# adapter.net
KiCad netlist of a schematic drawn in EAGLE
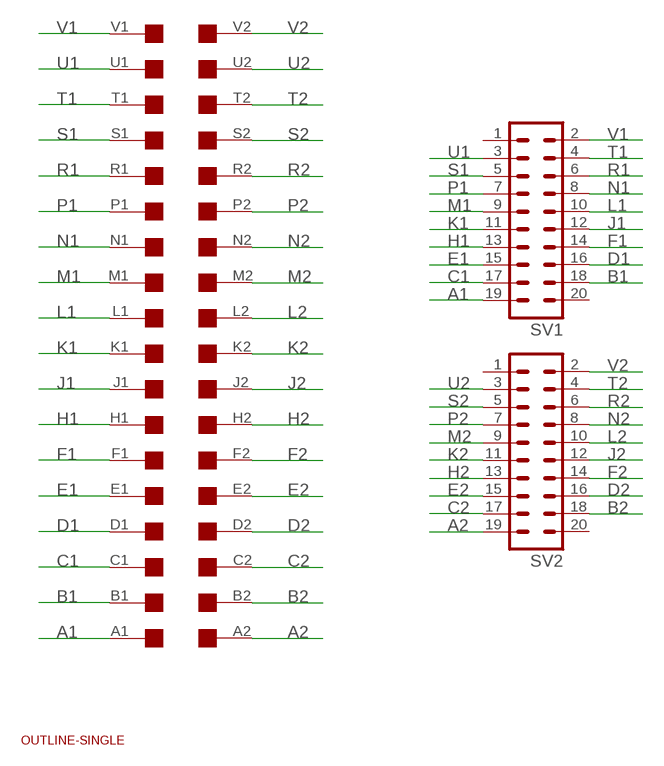
[diagram p0: schematic, sheet 1]

(export (version "E")
  (design (tool "Eeschema 10.0.6"))
  (components
    (comp (ref "SV1")
      (value "MA10-2W")
      (footprint "eagle-import:MA10-2W")
      (libsource (lib "eagle-import") (part "MA10-2W"))
    )
    (comp (ref "SV2")
      (value "MA10-2W")
      (footprint "eagle-import:MA10-2W")
      (libsource (lib "eagle-import") (part "MA10-2W"))
    )
    (comp (ref "U$1")
      (value "OUTLINE-SINGLE")
      (footprint "eagle-import:SINGLE")
      (libsource (lib "eagle-import") (part "OUTLINE-SINGLE"))
    )
    (comp (ref "U$2")
      (value "SINGLE")
      (footprint "eagle-import:EDGE-CON2")
      (libsource (lib "eagle-import") (part "SINGLE"))
    )
  )
  (nets
    (net (code "1") (name "/A1") (class "Default")
      (node (ref "SV1") (pin "19") (pinfunction "19_19") (pintype "passive"))
      (node (ref "U$2") (pin "A1") (pinfunction "1_A1") (pintype "bidirectional"))
    )
    (net (code "2") (name "/A2") (class "Default")
      (node (ref "SV2") (pin "19") (pinfunction "19_19") (pintype "passive"))
      (node (ref "U$2") (pin "A2") (pinfunction "1_A2") (pintype "bidirectional"))
    )
    (net (code "3") (name "/B1") (class "Default")
      (node (ref "SV1") (pin "18") (pinfunction "18_18") (pintype "passive"))
      (node (ref "U$2") (pin "B1") (pinfunction "1_B1") (pintype "bidirectional"))
    )
    (net (code "4") (name "/B2") (class "Default")
      (node (ref "SV2") (pin "18") (pinfunction "18_18") (pintype "passive"))
      (node (ref "U$2") (pin "B2") (pinfunction "1_B2") (pintype "bidirectional"))
    )
    (net (code "5") (name "/C1") (class "Default")
      (node (ref "SV1") (pin "17") (pinfunction "17_17") (pintype "passive"))
      (node (ref "U$2") (pin "C1") (pinfunction "1_C1") (pintype "bidirectional"))
    )
    (net (code "6") (name "/C2") (class "Default")
      (node (ref "SV2") (pin "17") (pinfunction "17_17") (pintype "passive"))
      (node (ref "U$2") (pin "C2") (pinfunction "1_C2") (pintype "bidirectional"))
    )
    (net (code "7") (name "/D1") (class "Default")
      (node (ref "SV1") (pin "16") (pinfunction "16_16") (pintype "passive"))
      (node (ref "U$2") (pin "D1") (pinfunction "1_D1") (pintype "bidirectional"))
    )
    (net (code "8") (name "/D2") (class "Default")
      (node (ref "SV2") (pin "16") (pinfunction "16_16") (pintype "passive"))
      (node (ref "U$2") (pin "D2") (pinfunction "1_D2") (pintype "bidirectional"))
    )
    (net (code "9") (name "/E1") (class "Default")
      (node (ref "SV1") (pin "15") (pinfunction "15_15") (pintype "passive"))
      (node (ref "U$2") (pin "E1") (pinfunction "1_E1") (pintype "bidirectional"))
    )
    (net (code "10") (name "/E2") (class "Default")
      (node (ref "SV2") (pin "15") (pinfunction "15_15") (pintype "passive"))
      (node (ref "U$2") (pin "E2") (pinfunction "1_E2") (pintype "bidirectional"))
    )
    (net (code "11") (name "/F1") (class "Default")
      (node (ref "SV1") (pin "14") (pinfunction "14_14") (pintype "passive"))
      (node (ref "U$2") (pin "F1") (pinfunction "1_F1") (pintype "bidirectional"))
    )
    (net (code "12") (name "/F2") (class "Default")
      (node (ref "SV2") (pin "14") (pinfunction "14_14") (pintype "passive"))
      (node (ref "U$2") (pin "F2") (pinfunction "1_F2") (pintype "bidirectional"))
    )
    (net (code "13") (name "/H1") (class "Default")
      (node (ref "SV1") (pin "13") (pinfunction "13_13") (pintype "passive"))
      (node (ref "U$2") (pin "H1") (pinfunction "1_H1") (pintype "bidirectional"))
    )
    (net (code "14") (name "/H2") (class "Default")
      (node (ref "SV2") (pin "13") (pinfunction "13_13") (pintype "passive"))
      (node (ref "U$2") (pin "H2") (pinfunction "1_H2") (pintype "bidirectional"))
    )
    (net (code "15") (name "/J1") (class "Default")
      (node (ref "SV1") (pin "12") (pinfunction "12_12") (pintype "passive"))
      (node (ref "U$2") (pin "J1") (pinfunction "1_J1") (pintype "bidirectional"))
    )
    (net (code "16") (name "/J2") (class "Default")
      (node (ref "SV2") (pin "12") (pinfunction "12_12") (pintype "passive"))
      (node (ref "U$2") (pin "J2") (pinfunction "1_J2") (pintype "bidirectional"))
    )
    (net (code "17") (name "/K1") (class "Default")
      (node (ref "SV1") (pin "11") (pinfunction "11_11") (pintype "passive"))
      (node (ref "U$2") (pin "K1") (pinfunction "1_K1") (pintype "bidirectional"))
    )
    (net (code "18") (name "/K2") (class "Default")
      (node (ref "SV2") (pin "11") (pinfunction "11_11") (pintype "passive"))
      (node (ref "U$2") (pin "K2") (pinfunction "1_K2") (pintype "bidirectional"))
    )
    (net (code "19") (name "/L1") (class "Default")
      (node (ref "SV1") (pin "10") (pinfunction "10_10") (pintype "passive"))
      (node (ref "U$2") (pin "L1") (pinfunction "1_L1") (pintype "bidirectional"))
    )
    (net (code "20") (name "/L2") (class "Default")
      (node (ref "SV2") (pin "10") (pinfunction "10_10") (pintype "passive"))
      (node (ref "U$2") (pin "L2") (pinfunction "1_L2") (pintype "bidirectional"))
    )
    (net (code "21") (name "/M1") (class "Default")
      (node (ref "SV1") (pin "9") (pinfunction "9_9") (pintype "passive"))
      (node (ref "U$2") (pin "M1") (pinfunction "1_M1") (pintype "bidirectional"))
    )
    (net (code "22") (name "/M2") (class "Default")
      (node (ref "SV2") (pin "9") (pinfunction "9_9") (pintype "passive"))
      (node (ref "U$2") (pin "M2") (pinfunction "1_M2") (pintype "bidirectional"))
    )
    (net (code "23") (name "/N1") (class "Default")
      (node (ref "SV1") (pin "8") (pinfunction "8_8") (pintype "passive"))
      (node (ref "U$2") (pin "N1") (pinfunction "1_N1") (pintype "bidirectional"))
    )
    (net (code "24") (name "/N2") (class "Default")
      (node (ref "SV2") (pin "8") (pinfunction "8_8") (pintype "passive"))
      (node (ref "U$2") (pin "N2") (pinfunction "1_N2") (pintype "bidirectional"))
    )
    (net (code "25") (name "/P1") (class "Default")
      (node (ref "SV1") (pin "7") (pinfunction "7_7") (pintype "passive"))
      (node (ref "U$2") (pin "P1") (pinfunction "1_P1") (pintype "bidirectional"))
    )
    (net (code "26") (name "/P2") (class "Default")
      (node (ref "SV2") (pin "7") (pinfunction "7_7") (pintype "passive"))
      (node (ref "U$2") (pin "P2") (pinfunction "1_P2") (pintype "bidirectional"))
    )
    (net (code "27") (name "/R1") (class "Default")
      (node (ref "SV1") (pin "6") (pinfunction "6_6") (pintype "passive"))
      (node (ref "U$2") (pin "R1") (pinfunction "1_R1") (pintype "bidirectional"))
    )
    (net (code "28") (name "/R2") (class "Default")
      (node (ref "SV2") (pin "6") (pinfunction "6_6") (pintype "passive"))
      (node (ref "U$2") (pin "R2") (pinfunction "1_R2") (pintype "bidirectional"))
    )
    (net (code "29") (name "/S1") (class "Default")
      (node (ref "SV1") (pin "5") (pinfunction "5_5") (pintype "passive"))
      (node (ref "U$2") (pin "S1") (pinfunction "1_S1") (pintype "bidirectional"))
    )
    (net (code "30") (name "/S2") (class "Default")
      (node (ref "SV2") (pin "5") (pinfunction "5_5") (pintype "passive"))
      (node (ref "U$2") (pin "S2") (pinfunction "1_S2") (pintype "bidirectional"))
    )
    (net (code "31") (name "/T1") (class "Default")
      (node (ref "SV1") (pin "4") (pinfunction "4_4") (pintype "passive"))
      (node (ref "U$2") (pin "T1") (pinfunction "1_T1") (pintype "bidirectional"))
    )
    (net (code "32") (name "/T2") (class "Default")
      (node (ref "SV2") (pin "4") (pinfunction "4_4") (pintype "passive"))
      (node (ref "U$2") (pin "T2") (pinfunction "1_T2") (pintype "bidirectional"))
    )
    (net (code "33") (name "/U1") (class "Default")
      (node (ref "SV1") (pin "3") (pinfunction "3_3") (pintype "passive"))
      (node (ref "U$2") (pin "U1") (pinfunction "1_U1") (pintype "bidirectional"))
    )
    (net (code "34") (name "/U2") (class "Default")
      (node (ref "SV2") (pin "3") (pinfunction "3_3") (pintype "passive"))
      (node (ref "U$2") (pin "U2") (pinfunction "1_U2") (pintype "bidirectional"))
    )
    (net (code "35") (name "/V1") (class "Default")
      (node (ref "SV1") (pin "2") (pinfunction "2_2") (pintype "passive"))
      (node (ref "U$2") (pin "V1") (pinfunction "1_V1") (pintype "bidirectional"))
    )
    (net (code "36") (name "/V2") (class "Default")
      (node (ref "SV2") (pin "2") (pinfunction "2_2") (pintype "passive"))
      (node (ref "U$2") (pin "V2") (pinfunction "1_V2") (pintype "bidirectional"))
    )
    (net (code "37") (name "unconnected-(SV1-Pad1)") (class "Default")
      (node (ref "SV1") (pin "1") (pinfunction "1_1") (pintype "passive"))
    )
    (net (code "38") (name "unconnected-(SV1-Pad20)") (class "Default")
      (node (ref "SV1") (pin "20") (pinfunction "20_20") (pintype "passive"))
    )
    (net (code "39") (name "unconnected-(SV2-Pad1)") (class "Default")
      (node (ref "SV2") (pin "1") (pinfunction "1_1") (pintype "passive"))
    )
    (net (code "40") (name "unconnected-(SV2-Pad20)") (class "Default")
      (node (ref "SV2") (pin "20") (pinfunction "20_20") (pintype "passive"))
    )
  )
)
